# BUS_SPLIT_1.net
KiCad netlist of a schematic drawn in EAGLE
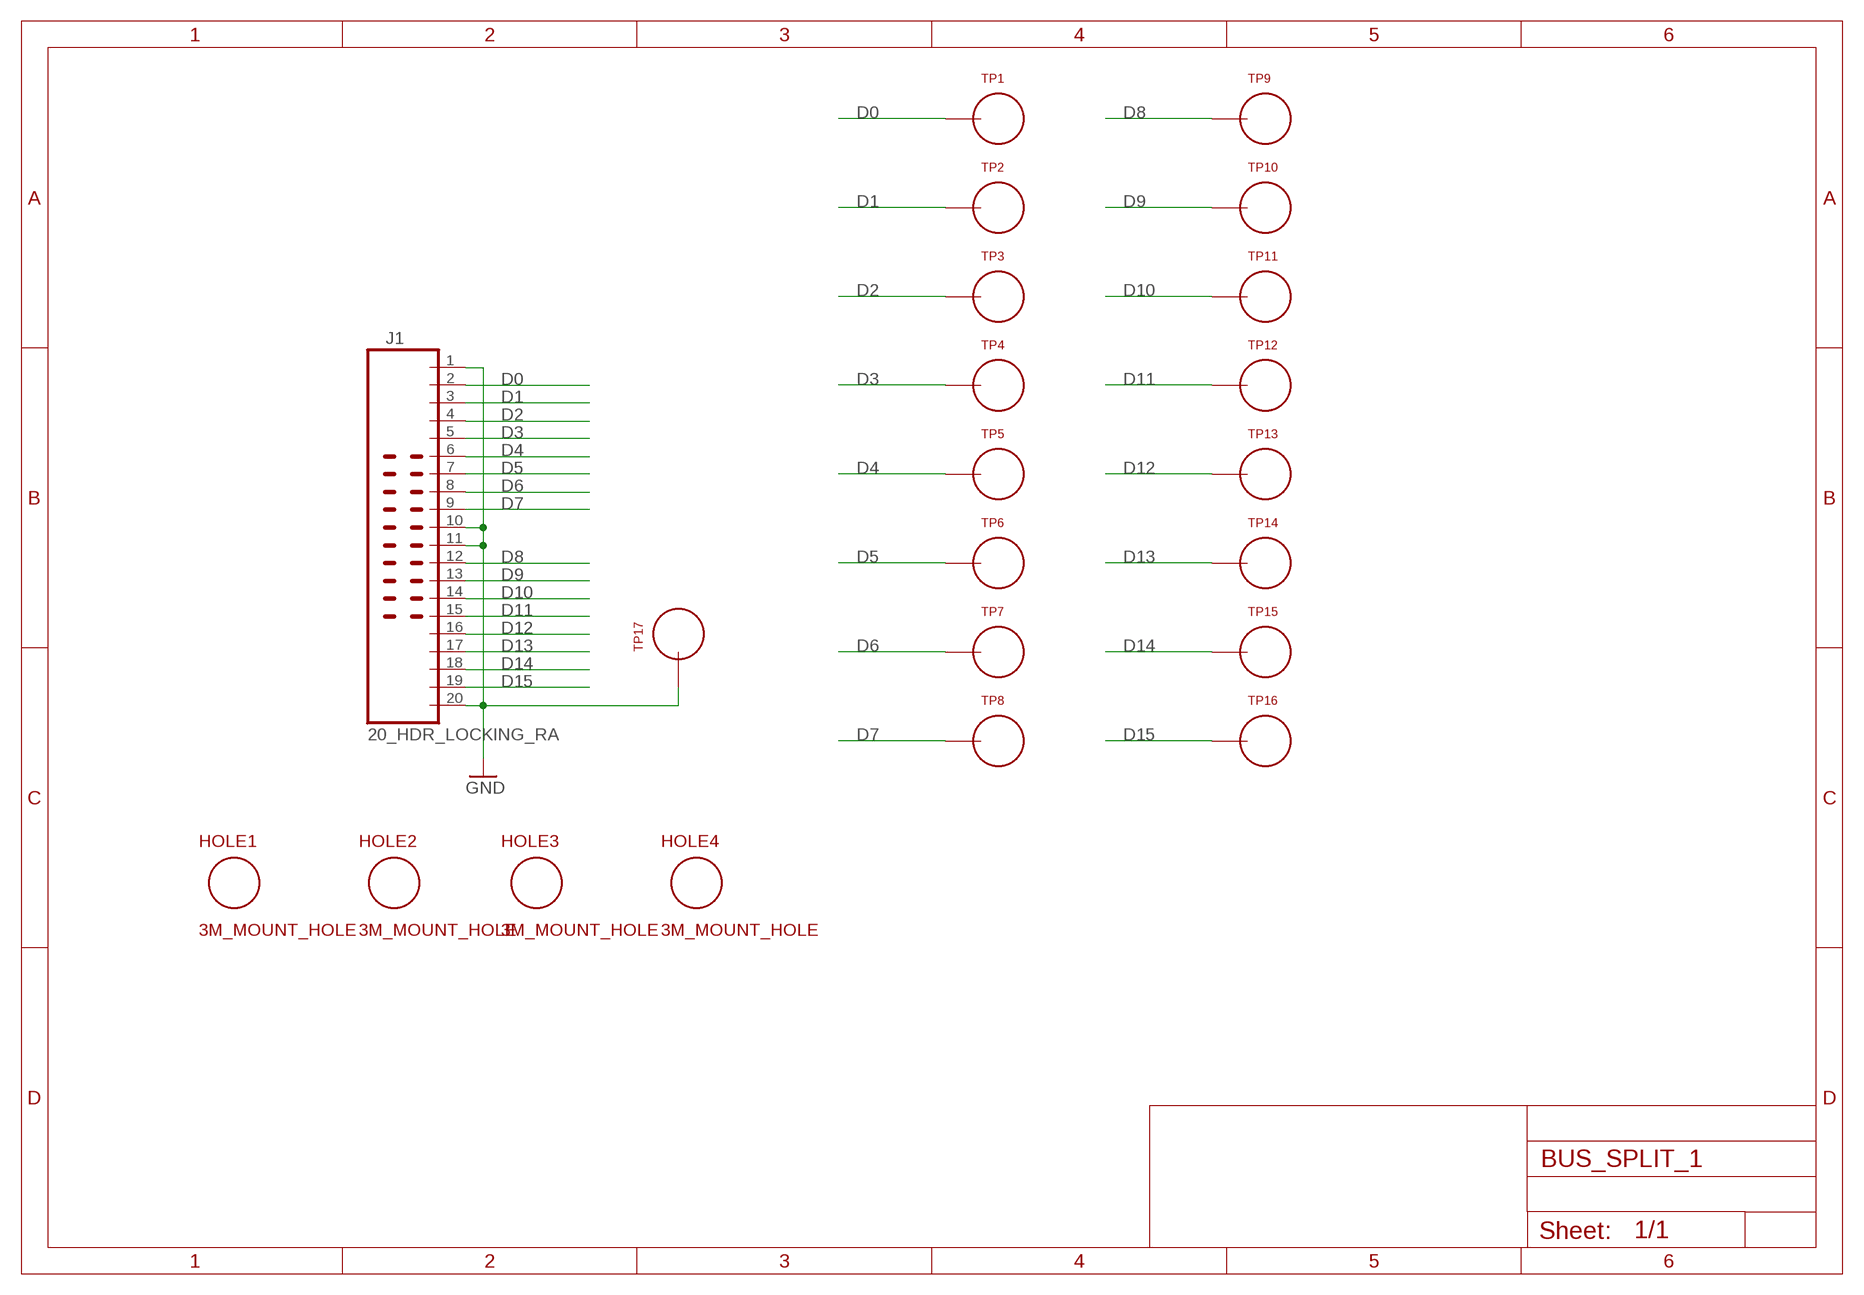
[diagram p0: schematic, sheet 1]

(export (version "E")
  (design (tool "Eeschema 10.0.6"))
  (components
    (comp (ref "HOLE1")
      (value "3M_MOUNT_HOLE")
      (footprint "eagle-import:3M_HOLE")
      (libsource (lib "eagle-import") (part "3M_MOUNT_HOLE"))
    )
    (comp (ref "HOLE2")
      (value "3M_MOUNT_HOLE")
      (footprint "eagle-import:3M_HOLE")
      (libsource (lib "eagle-import") (part "3M_MOUNT_HOLE"))
    )
    (comp (ref "HOLE3")
      (value "3M_MOUNT_HOLE")
      (footprint "eagle-import:3M_HOLE")
      (libsource (lib "eagle-import") (part "3M_MOUNT_HOLE"))
    )
    (comp (ref "HOLE4")
      (value "3M_MOUNT_HOLE")
      (footprint "eagle-import:3M_HOLE")
      (libsource (lib "eagle-import") (part "3M_MOUNT_HOLE"))
    )
    (comp (ref "J1")
      (value "20_HDR_LOCKING_RA")
      (footprint "eagle-import:20_HDR_LOCKING_RA")
      (libsource (lib "eagle-import") (part "20_HDR_LOCKING_RA"))
    )
    (comp (ref "TP1")
      (value "TEST_LOOP")
      (footprint "eagle-import:TEST_LOOP")
      (libsource (lib "eagle-import") (part "TEST_LOOP"))
    )
    (comp (ref "TP2")
      (value "TEST_LOOP")
      (footprint "eagle-import:TEST_LOOP")
      (libsource (lib "eagle-import") (part "TEST_LOOP"))
    )
    (comp (ref "TP3")
      (value "TEST_LOOP")
      (footprint "eagle-import:TEST_LOOP")
      (libsource (lib "eagle-import") (part "TEST_LOOP"))
    )
    (comp (ref "TP4")
      (value "TEST_LOOP")
      (footprint "eagle-import:TEST_LOOP")
      (libsource (lib "eagle-import") (part "TEST_LOOP"))
    )
    (comp (ref "TP5")
      (value "TEST_LOOP")
      (footprint "eagle-import:TEST_LOOP")
      (libsource (lib "eagle-import") (part "TEST_LOOP"))
    )
    (comp (ref "TP6")
      (value "TEST_LOOP")
      (footprint "eagle-import:TEST_LOOP")
      (libsource (lib "eagle-import") (part "TEST_LOOP"))
    )
    (comp (ref "TP7")
      (value "TEST_LOOP")
      (footprint "eagle-import:TEST_LOOP")
      (libsource (lib "eagle-import") (part "TEST_LOOP"))
    )
    (comp (ref "TP8")
      (value "TEST_LOOP")
      (footprint "eagle-import:TEST_LOOP")
      (libsource (lib "eagle-import") (part "TEST_LOOP"))
    )
    (comp (ref "TP9")
      (value "TEST_LOOP")
      (footprint "eagle-import:TEST_LOOP")
      (libsource (lib "eagle-import") (part "TEST_LOOP"))
    )
    (comp (ref "TP10")
      (value "TEST_LOOP")
      (footprint "eagle-import:TEST_LOOP")
      (libsource (lib "eagle-import") (part "TEST_LOOP"))
    )
    (comp (ref "TP11")
      (value "TEST_LOOP")
      (footprint "eagle-import:TEST_LOOP")
      (libsource (lib "eagle-import") (part "TEST_LOOP"))
    )
    (comp (ref "TP12")
      (value "TEST_LOOP")
      (footprint "eagle-import:TEST_LOOP")
      (libsource (lib "eagle-import") (part "TEST_LOOP"))
    )
    (comp (ref "TP13")
      (value "TEST_LOOP")
      (footprint "eagle-import:TEST_LOOP")
      (libsource (lib "eagle-import") (part "TEST_LOOP"))
    )
    (comp (ref "TP14")
      (value "TEST_LOOP")
      (footprint "eagle-import:TEST_LOOP")
      (libsource (lib "eagle-import") (part "TEST_LOOP"))
    )
    (comp (ref "TP15")
      (value "TEST_LOOP")
      (footprint "eagle-import:TEST_LOOP")
      (libsource (lib "eagle-import") (part "TEST_LOOP"))
    )
    (comp (ref "TP16")
      (value "TEST_LOOP")
      (footprint "eagle-import:TEST_LOOP")
      (libsource (lib "eagle-import") (part "TEST_LOOP"))
    )
    (comp (ref "TP17")
      (value "TEST_LOOP")
      (footprint "eagle-import:TEST_LOOP")
      (libsource (lib "eagle-import") (part "TEST_LOOP"))
    )
  )
  (nets
    (net (code "1") (name "/D0") (class "Default")
      (node (ref "J1") (pin "2") (pinfunction "2_2") (pintype "bidirectional"))
      (node (ref "TP1") (pin "P$1") (pinfunction "P$1_P$1") (pintype "bidirectional"))
    )
    (net (code "2") (name "/D1") (class "Default")
      (node (ref "J1") (pin "3") (pinfunction "3_3") (pintype "bidirectional"))
      (node (ref "TP2") (pin "P$1") (pinfunction "P$1_P$1") (pintype "bidirectional"))
    )
    (net (code "3") (name "/D2") (class "Default")
      (node (ref "J1") (pin "4") (pinfunction "4_4") (pintype "bidirectional"))
      (node (ref "TP3") (pin "P$1") (pinfunction "P$1_P$1") (pintype "bidirectional"))
    )
    (net (code "4") (name "/D3") (class "Default")
      (node (ref "J1") (pin "5") (pinfunction "5_5") (pintype "bidirectional"))
      (node (ref "TP4") (pin "P$1") (pinfunction "P$1_P$1") (pintype "bidirectional"))
    )
    (net (code "5") (name "/D4") (class "Default")
      (node (ref "J1") (pin "6") (pinfunction "6_6") (pintype "bidirectional"))
      (node (ref "TP5") (pin "P$1") (pinfunction "P$1_P$1") (pintype "bidirectional"))
    )
    (net (code "6") (name "/D5") (class "Default")
      (node (ref "J1") (pin "7") (pinfunction "7_7") (pintype "bidirectional"))
      (node (ref "TP6") (pin "P$1") (pinfunction "P$1_P$1") (pintype "bidirectional"))
    )
    (net (code "7") (name "/D6") (class "Default")
      (node (ref "J1") (pin "8") (pinfunction "8_8") (pintype "bidirectional"))
      (node (ref "TP7") (pin "P$1") (pinfunction "P$1_P$1") (pintype "bidirectional"))
    )
    (net (code "8") (name "/D7") (class "Default")
      (node (ref "J1") (pin "9") (pinfunction "9_9") (pintype "bidirectional"))
      (node (ref "TP8") (pin "P$1") (pinfunction "P$1_P$1") (pintype "bidirectional"))
    )
    (net (code "9") (name "/D8") (class "Default")
      (node (ref "J1") (pin "12") (pinfunction "12_12") (pintype "bidirectional"))
      (node (ref "TP9") (pin "P$1") (pinfunction "P$1_P$1") (pintype "bidirectional"))
    )
    (net (code "10") (name "/D9") (class "Default")
      (node (ref "J1") (pin "13") (pinfunction "13_13") (pintype "bidirectional"))
      (node (ref "TP10") (pin "P$1") (pinfunction "P$1_P$1") (pintype "bidirectional"))
    )
    (net (code "11") (name "/D10") (class "Default")
      (node (ref "J1") (pin "14") (pinfunction "14_14") (pintype "bidirectional"))
      (node (ref "TP11") (pin "P$1") (pinfunction "P$1_P$1") (pintype "bidirectional"))
    )
    (net (code "12") (name "/D11") (class "Default")
      (node (ref "J1") (pin "15") (pinfunction "15_15") (pintype "bidirectional"))
      (node (ref "TP12") (pin "P$1") (pinfunction "P$1_P$1") (pintype "bidirectional"))
    )
    (net (code "13") (name "/D12") (class "Default")
      (node (ref "J1") (pin "16") (pinfunction "16_16") (pintype "bidirectional"))
      (node (ref "TP13") (pin "P$1") (pinfunction "P$1_P$1") (pintype "bidirectional"))
    )
    (net (code "14") (name "/D13") (class "Default")
      (node (ref "J1") (pin "17") (pinfunction "17_17") (pintype "bidirectional"))
      (node (ref "TP14") (pin "P$1") (pinfunction "P$1_P$1") (pintype "bidirectional"))
    )
    (net (code "15") (name "/D14") (class "Default")
      (node (ref "J1") (pin "18") (pinfunction "18_18") (pintype "bidirectional"))
      (node (ref "TP15") (pin "P$1") (pinfunction "P$1_P$1") (pintype "bidirectional"))
    )
    (net (code "16") (name "/D15") (class "Default")
      (node (ref "J1") (pin "19") (pinfunction "19_19") (pintype "bidirectional"))
      (node (ref "TP16") (pin "P$1") (pinfunction "P$1_P$1") (pintype "bidirectional"))
    )
    (net (code "17") (name "GND") (class "Default")
      (node (ref "J1") (pin "1") (pinfunction "1_1") (pintype "bidirectional"))
      (node (ref "J1") (pin "10") (pinfunction "10_10") (pintype "bidirectional"))
      (node (ref "J1") (pin "11") (pinfunction "11_11") (pintype "bidirectional"))
      (node (ref "J1") (pin "20") (pinfunction "20_20") (pintype "bidirectional"))
      (node (ref "TP17") (pin "P$1") (pinfunction "P$1_P$1") (pintype "bidirectional"))
    )
  )
)
